# COMMUNICATION.net
KiCad netlist of a schematic drawn in Altium Designer
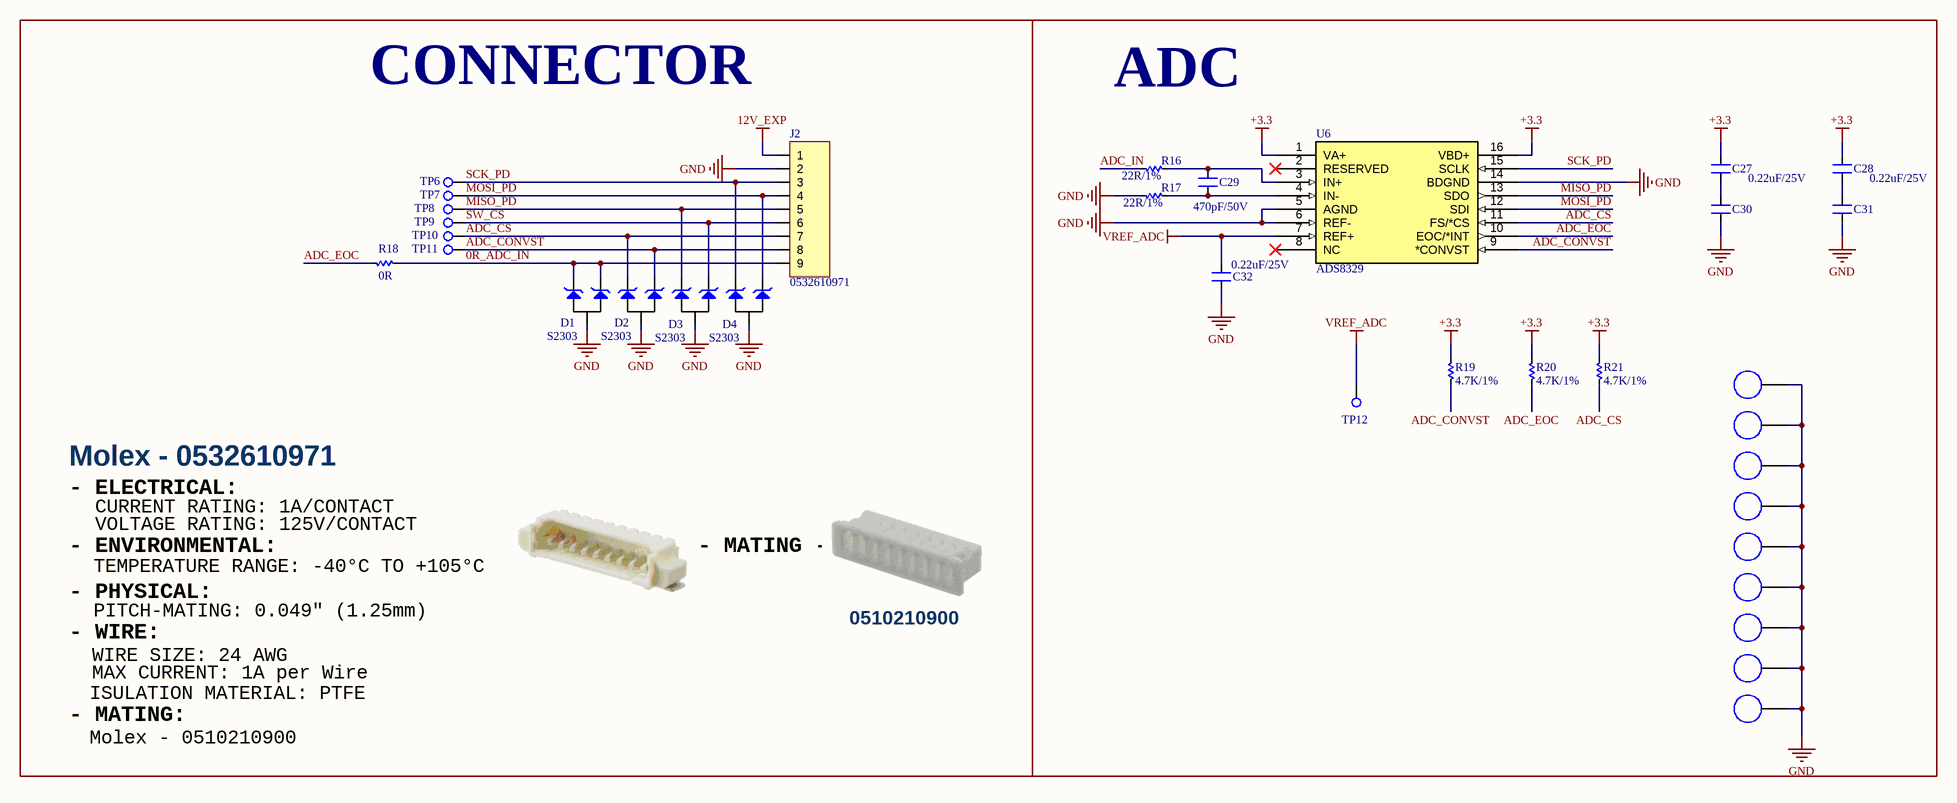
[diagram p0: COMMUNICATION.SchDoc]

(export (version "E")
  (design (tool "Eeschema 10.0.6"))
  (components
    (comp (ref "C27")
      (value "0.22uF/25V")
      (footprint "CN-SMD-0603")
      (description "CL10B224KA8NNNC")
      (libsource (lib "Capacitors") (part "CM"))
    )
    (comp (ref "C28")
      (value "0.22uF/25V")
      (footprint "CN-SMD-0603")
      (description "CL10B224KA8NNNC")
      (libsource (lib "Capacitors") (part "CM"))
    )
    (comp (ref "C29")
      (value "470pF/50V")
      (footprint "CN-SMD-0603")
      (description "CL10B471KB8NNNC")
      (libsource (lib "Capacitors") (part "CM"))
    )
    (comp (ref "C30")
      (value "0.22uF/25V")
      (footprint "CN-SMD-0603")
      (description "CL10B224KA8NNNC")
      (libsource (lib "Capacitors") (part "CM"))
    )
    (comp (ref "C31")
      (value "0.22uF/25V")
      (footprint "CN-SMD-0603")
      (description "CL10B224KA8NNNC")
      (libsource (lib "Capacitors") (part "CM"))
    )
    (comp (ref "C32")
      (value "0.22uF/25V")
      (footprint "CN-SMD-0603")
      (description "CL10B224KA8NNNC")
      (libsource (lib "Capacitors") (part "CM"))
    )
    (comp (ref "D1") (value "S2303") (footprint "SOT23-123") (libsource (lib "Library") (part "S2303")))
    (comp (ref "D2") (value "S2303") (footprint "SOT23-123") (libsource (lib "Library") (part "S2303")))
    (comp (ref "D3") (value "S2303") (footprint "SOT23-123") (libsource (lib "Library") (part "S2303")))
    (comp (ref "D4") (value "S2303") (footprint "SOT23-123") (libsource (lib "Library") (part "S2303")))
    (comp (ref "H1") (value "HOLD") (footprint "M3 - 6mm") (libsource (lib "Library_HUNG") (part "PAD_HOLD")))
    (comp (ref "H2") (value "HOLD") (footprint "M3 - 6mm") (libsource (lib "Library_HUNG") (part "PAD_HOLD")))
    (comp (ref "H3") (value "HOLD") (footprint "M3 - 6mm") (libsource (lib "Library_HUNG") (part "PAD_HOLD")))
    (comp (ref "H4") (value "HOLD") (footprint "M3 - 6mm") (libsource (lib "Library_HUNG") (part "PAD_HOLD")))
    (comp (ref "H5") (value "HOLD") (footprint "M3 - 6mm") (libsource (lib "Library_HUNG") (part "PAD_HOLD")))
    (comp (ref "H6") (value "HOLD") (footprint "M3 - 6mm") (libsource (lib "Library_HUNG") (part "PAD_HOLD")))
    (comp (ref "H7") (value "HOLD") (footprint "M3 - 6mm") (libsource (lib "Library_HUNG") (part "PAD_HOLD")))
    (comp (ref "H8") (value "HOLD") (footprint "M3 - 6mm") (libsource (lib "Library_HUNG") (part "PAD_HOLD")))
    (comp (ref "H9") (value "HOLD") (footprint "M3 - 6mm") (libsource (lib "Library_HUNG") (part "PAD_HOLD")))
    (comp (ref "J2")
      (value "0532610971")
      (footprint "0532610971")
      (fields
        (field (name "MANUFACTURER") "Würth Elektronik eiSos GmbH")
        (field (name "PARTNO") "613009143121")
        (field (name "CREATED BY") "Karrer Zheng")
      )
      (libsource (lib "Library") (part "JP9"))
    )
    (comp (ref "R16")
      (value "22R/1%")
      (footprint "RES-SMD-0603")
      (description "ERJ-3EKF22R0V")
      (fields
        (field (name "MANUFACTURER") "Generic Components")
        (field (name "PUBLISHER") "Altium Hobart Technology Centre")
      )
      (libsource (lib "Library") (part "Res-SMD"))
    )
    (comp (ref "R17")
      (value "22R/1%")
      (footprint "RES-SMD-0603")
      (description "ERJ-3EKF22R0V")
      (fields
        (field (name "MANUFACTURER") "Generic Components")
        (field (name "PUBLISHER") "Altium Hobart Technology Centre")
      )
      (libsource (lib "Library") (part "Res-SMD"))
    )
    (comp (ref "R18")
      (value "0R")
      (footprint "RES-SMD-0603")
      (description "ERJ-3GEY0R00V")
      (fields
        (field (name "MANUFACTURER") "Generic Components")
        (field (name "PUBLISHER") "Altium Hobart Technology Centre")
      )
      (libsource (lib "Library") (part "Res-SMD"))
    )
    (comp (ref "R19")
      (value "4.7K/1%")
      (footprint "RES-SMD-0603")
      (description "ERJ-3EKF4701V")
      (fields
        (field (name "MANUFACTURER") "Generic Components")
        (field (name "PUBLISHER") "Altium Hobart Technology Centre")
      )
      (libsource (lib "Library") (part "Res-SMD"))
    )
    (comp (ref "R20")
      (value "4.7K/1%")
      (footprint "RES-SMD-0603")
      (description "ERJ-3EKF4701V")
      (fields
        (field (name "MANUFACTURER") "Generic Components")
        (field (name "PUBLISHER") "Altium Hobart Technology Centre")
      )
      (libsource (lib "Library") (part "Res-SMD"))
    )
    (comp (ref "R21")
      (value "4.7K/1%")
      (footprint "RES-SMD-0603")
      (description "ERJ-3EKF4701V")
      (fields
        (field (name "MANUFACTURER") "Generic Components")
        (field (name "PUBLISHER") "Altium Hobart Technology Centre")
      )
      (libsource (lib "Library") (part "Res-SMD"))
    )
    (comp (ref "TP6")
      (value "Test_Point")
      (footprint "TESTPOINT")
      (libsource (lib "Library_HUNG") (part "Test_Point"))
    )
    (comp (ref "TP7")
      (value "Test_Point")
      (footprint "TESTPOINT")
      (libsource (lib "Library_HUNG") (part "Test_Point"))
    )
    (comp (ref "TP8")
      (value "Test_Point")
      (footprint "TESTPOINT")
      (libsource (lib "Library_HUNG") (part "Test_Point"))
    )
    (comp (ref "TP9")
      (value "Test_Point")
      (footprint "TESTPOINT")
      (libsource (lib "Library_HUNG") (part "Test_Point"))
    )
    (comp (ref "TP10")
      (value "Test_Point")
      (footprint "TESTPOINT")
      (libsource (lib "Library_HUNG") (part "Test_Point"))
    )
    (comp (ref "TP11")
      (value "Test_Point")
      (footprint "TESTPOINT")
      (libsource (lib "Library_HUNG") (part "Test_Point"))
    )
    (comp (ref "TP12")
      (value "Test_Point")
      (footprint "TESTPOINT")
      (libsource (lib "Library_HUNG") (part "Test_Point"))
    )
    (comp (ref "U6") (value "ADS8329") (footprint "TSSOP16") (libsource (lib "Library") (part "ADS8327")))
  )
  (nets
    (net (code "1") (name "+3.3") (class "Default")
      (node (ref "C27") (pin "2") (pinfunction "2_2") (pintype "passive"))
      (node (ref "C28") (pin "2") (pinfunction "2_2") (pintype "passive"))
      (node (ref "R19") (pin "2") (pinfunction "2_2") (pintype "passive"))
      (node (ref "R20") (pin "2") (pinfunction "2_2") (pintype "passive"))
      (node (ref "R21") (pin "2") (pinfunction "2_2") (pintype "passive"))
      (node (ref "U6") (pin "1") (pinfunction "VA+_1") (pintype "power_in"))
      (node (ref "U6") (pin "16") (pinfunction "VBD+_16") (pintype "power_in"))
    )
    (net (code "2") (name "/0R_ADC_IN") (class "Default")
      (node (ref "D1") (pin "1") (pintype "passive"))
      (node (ref "D1") (pin "3") (pintype "passive"))
      (node (ref "J2") (pin "9") (pinfunction "9_9") (pintype "passive"))
      (node (ref "R18") (pin "1") (pinfunction "1_1") (pintype "passive"))
    )
    (net (code "3") (name "/ADC_CONVST") (class "Default")
      (node (ref "D2") (pin "3") (pintype "passive"))
      (node (ref "J2") (pin "8") (pinfunction "8_8") (pintype "passive"))
      (node (ref "R19") (pin "1") (pinfunction "1_1") (pintype "passive"))
      (node (ref "TP11") (pin "1") (pintype "power_in"))
      (node (ref "U6") (pin "9") (pinfunction "*CONVST_9") (pintype "input"))
    )
    (net (code "4") (name "/ADC_CS") (class "Default")
      (node (ref "D2") (pin "1") (pintype "passive"))
      (node (ref "J2") (pin "7") (pinfunction "7_7") (pintype "passive"))
      (node (ref "R21") (pin "1") (pinfunction "1_1") (pintype "passive"))
      (node (ref "TP10") (pin "1") (pintype "power_in"))
      (node (ref "U6") (pin "11") (pinfunction "FS/*CS_11") (pintype "input"))
    )
    (net (code "5") (name "/ADC_EOC") (class "Default")
      (node (ref "R18") (pin "2") (pinfunction "2_2") (pintype "passive"))
      (node (ref "R20") (pin "1") (pinfunction "1_1") (pintype "passive"))
      (node (ref "U6") (pin "10") (pinfunction "EOC/*INT_10") (pintype "output"))
    )
    (net (code "6") (name "/ADC_IN") (class "Default")
      (node (ref "R16") (pin "2") (pinfunction "2_2") (pintype "passive"))
    )
    (net (code "7") (name "/MISO_PD") (class "Default")
      (node (ref "D3") (pin "1") (pintype "passive"))
      (node (ref "J2") (pin "5") (pinfunction "5_5") (pintype "passive"))
      (node (ref "TP8") (pin "1") (pintype "power_in"))
      (node (ref "U6") (pin "13") (pinfunction "SDO_13") (pintype "output"))
    )
    (net (code "8") (name "/MOSI_PD") (class "Default")
      (node (ref "D4") (pin "3") (pintype "passive"))
      (node (ref "J2") (pin "4") (pinfunction "4_4") (pintype "passive"))
      (node (ref "TP7") (pin "1") (pintype "power_in"))
      (node (ref "U6") (pin "12") (pinfunction "SDI_12") (pintype "input"))
    )
    (net (code "9") (name "/SCK_PD") (class "Default")
      (node (ref "D4") (pin "1") (pintype "passive"))
      (node (ref "J2") (pin "3") (pinfunction "3_3") (pintype "passive"))
      (node (ref "TP6") (pin "1") (pintype "power_in"))
      (node (ref "U6") (pin "15") (pinfunction "SCLK_15") (pintype "input"))
    )
    (net (code "10") (name "/SW_CS") (class "Default")
      (node (ref "D3") (pin "3") (pintype "passive"))
      (node (ref "J2") (pin "6") (pinfunction "6_6") (pintype "passive"))
      (node (ref "TP9") (pin "1") (pintype "power_in"))
    )
    (net (code "11") (name "12V_EXP") (class "Default")
      (node (ref "J2") (pin "1") (pinfunction "1_1") (pintype "passive"))
    )
    (net (code "12") (name "GND") (class "Default")
      (node (ref "C30") (pin "1") (pinfunction "1_1") (pintype "passive"))
      (node (ref "C31") (pin "1") (pinfunction "1_1") (pintype "passive"))
      (node (ref "C32") (pin "1") (pinfunction "1_1") (pintype "passive"))
      (node (ref "D1") (pin "2") (pintype "passive"))
      (node (ref "D2") (pin "2") (pintype "passive"))
      (node (ref "D3") (pin "2") (pintype "passive"))
      (node (ref "D4") (pin "2") (pintype "passive"))
      (node (ref "H1") (pin "1") (pintype "power_in"))
      (node (ref "H2") (pin "1") (pintype "power_in"))
      (node (ref "H3") (pin "1") (pintype "power_in"))
      (node (ref "H4") (pin "1") (pintype "power_in"))
      (node (ref "H5") (pin "1") (pintype "power_in"))
      (node (ref "H6") (pin "1") (pintype "power_in"))
      (node (ref "H7") (pin "1") (pintype "power_in"))
      (node (ref "H8") (pin "1") (pintype "power_in"))
      (node (ref "H9") (pin "1") (pintype "power_in"))
      (node (ref "J2") (pin "2") (pinfunction "2_2") (pintype "passive"))
      (node (ref "R17") (pin "2") (pinfunction "2_2") (pintype "passive"))
      (node (ref "U6") (pin "14") (pinfunction "BDGND_14") (pintype "power_in"))
      (node (ref "U6") (pin "5") (pinfunction "AGND_5") (pintype "power_in"))
      (node (ref "U6") (pin "6") (pinfunction "REF-_6") (pintype "input"))
    )
    (net (code "13") (name "Net-(C27-Pad1)") (class "Default")
      (node (ref "C27") (pin "1") (pinfunction "1_1") (pintype "passive"))
      (node (ref "C30") (pin "2") (pinfunction "2_2") (pintype "passive"))
    )
    (net (code "14") (name "Net-(C28-Pad1)") (class "Default")
      (node (ref "C28") (pin "1") (pinfunction "1_1") (pintype "passive"))
      (node (ref "C31") (pin "2") (pinfunction "2_2") (pintype "passive"))
    )
    (net (code "15") (name "Net-(U6-IN+)") (class "Default")
      (node (ref "C29") (pin "2") (pinfunction "2_2") (pintype "passive"))
      (node (ref "R16") (pin "1") (pinfunction "1_1") (pintype "passive"))
      (node (ref "U6") (pin "3") (pinfunction "IN+_3") (pintype "input"))
    )
    (net (code "16") (name "Net-(U6-IN-)") (class "Default")
      (node (ref "C29") (pin "1") (pinfunction "1_1") (pintype "passive"))
      (node (ref "R17") (pin "1") (pinfunction "1_1") (pintype "passive"))
      (node (ref "U6") (pin "4") (pinfunction "IN-_4") (pintype "input"))
    )
    (net (code "17") (name "VREF_ADC") (class "Default")
      (node (ref "C32") (pin "2") (pinfunction "2_2") (pintype "passive"))
      (node (ref "TP12") (pin "1") (pintype "power_in"))
      (node (ref "U6") (pin "7") (pinfunction "REF+_7") (pintype "input"))
    )
    (net (code "18") (name "unconnected-(U6-NC-Pad8)") (class "Default")
      (node (ref "U6") (pin "8") (pinfunction "NC_8") (pintype "passive+no_connect"))
    )
    (net (code "19") (name "unconnected-(U6-RESERVED-Pad2)") (class "Default")
      (node (ref "U6") (pin "2") (pinfunction "RESERVED_2") (pintype "passive+no_connect"))
    )
  )
)
